# Adorkable_Base.net
KiCad netlist of a schematic drawn in EasyEDA Pro
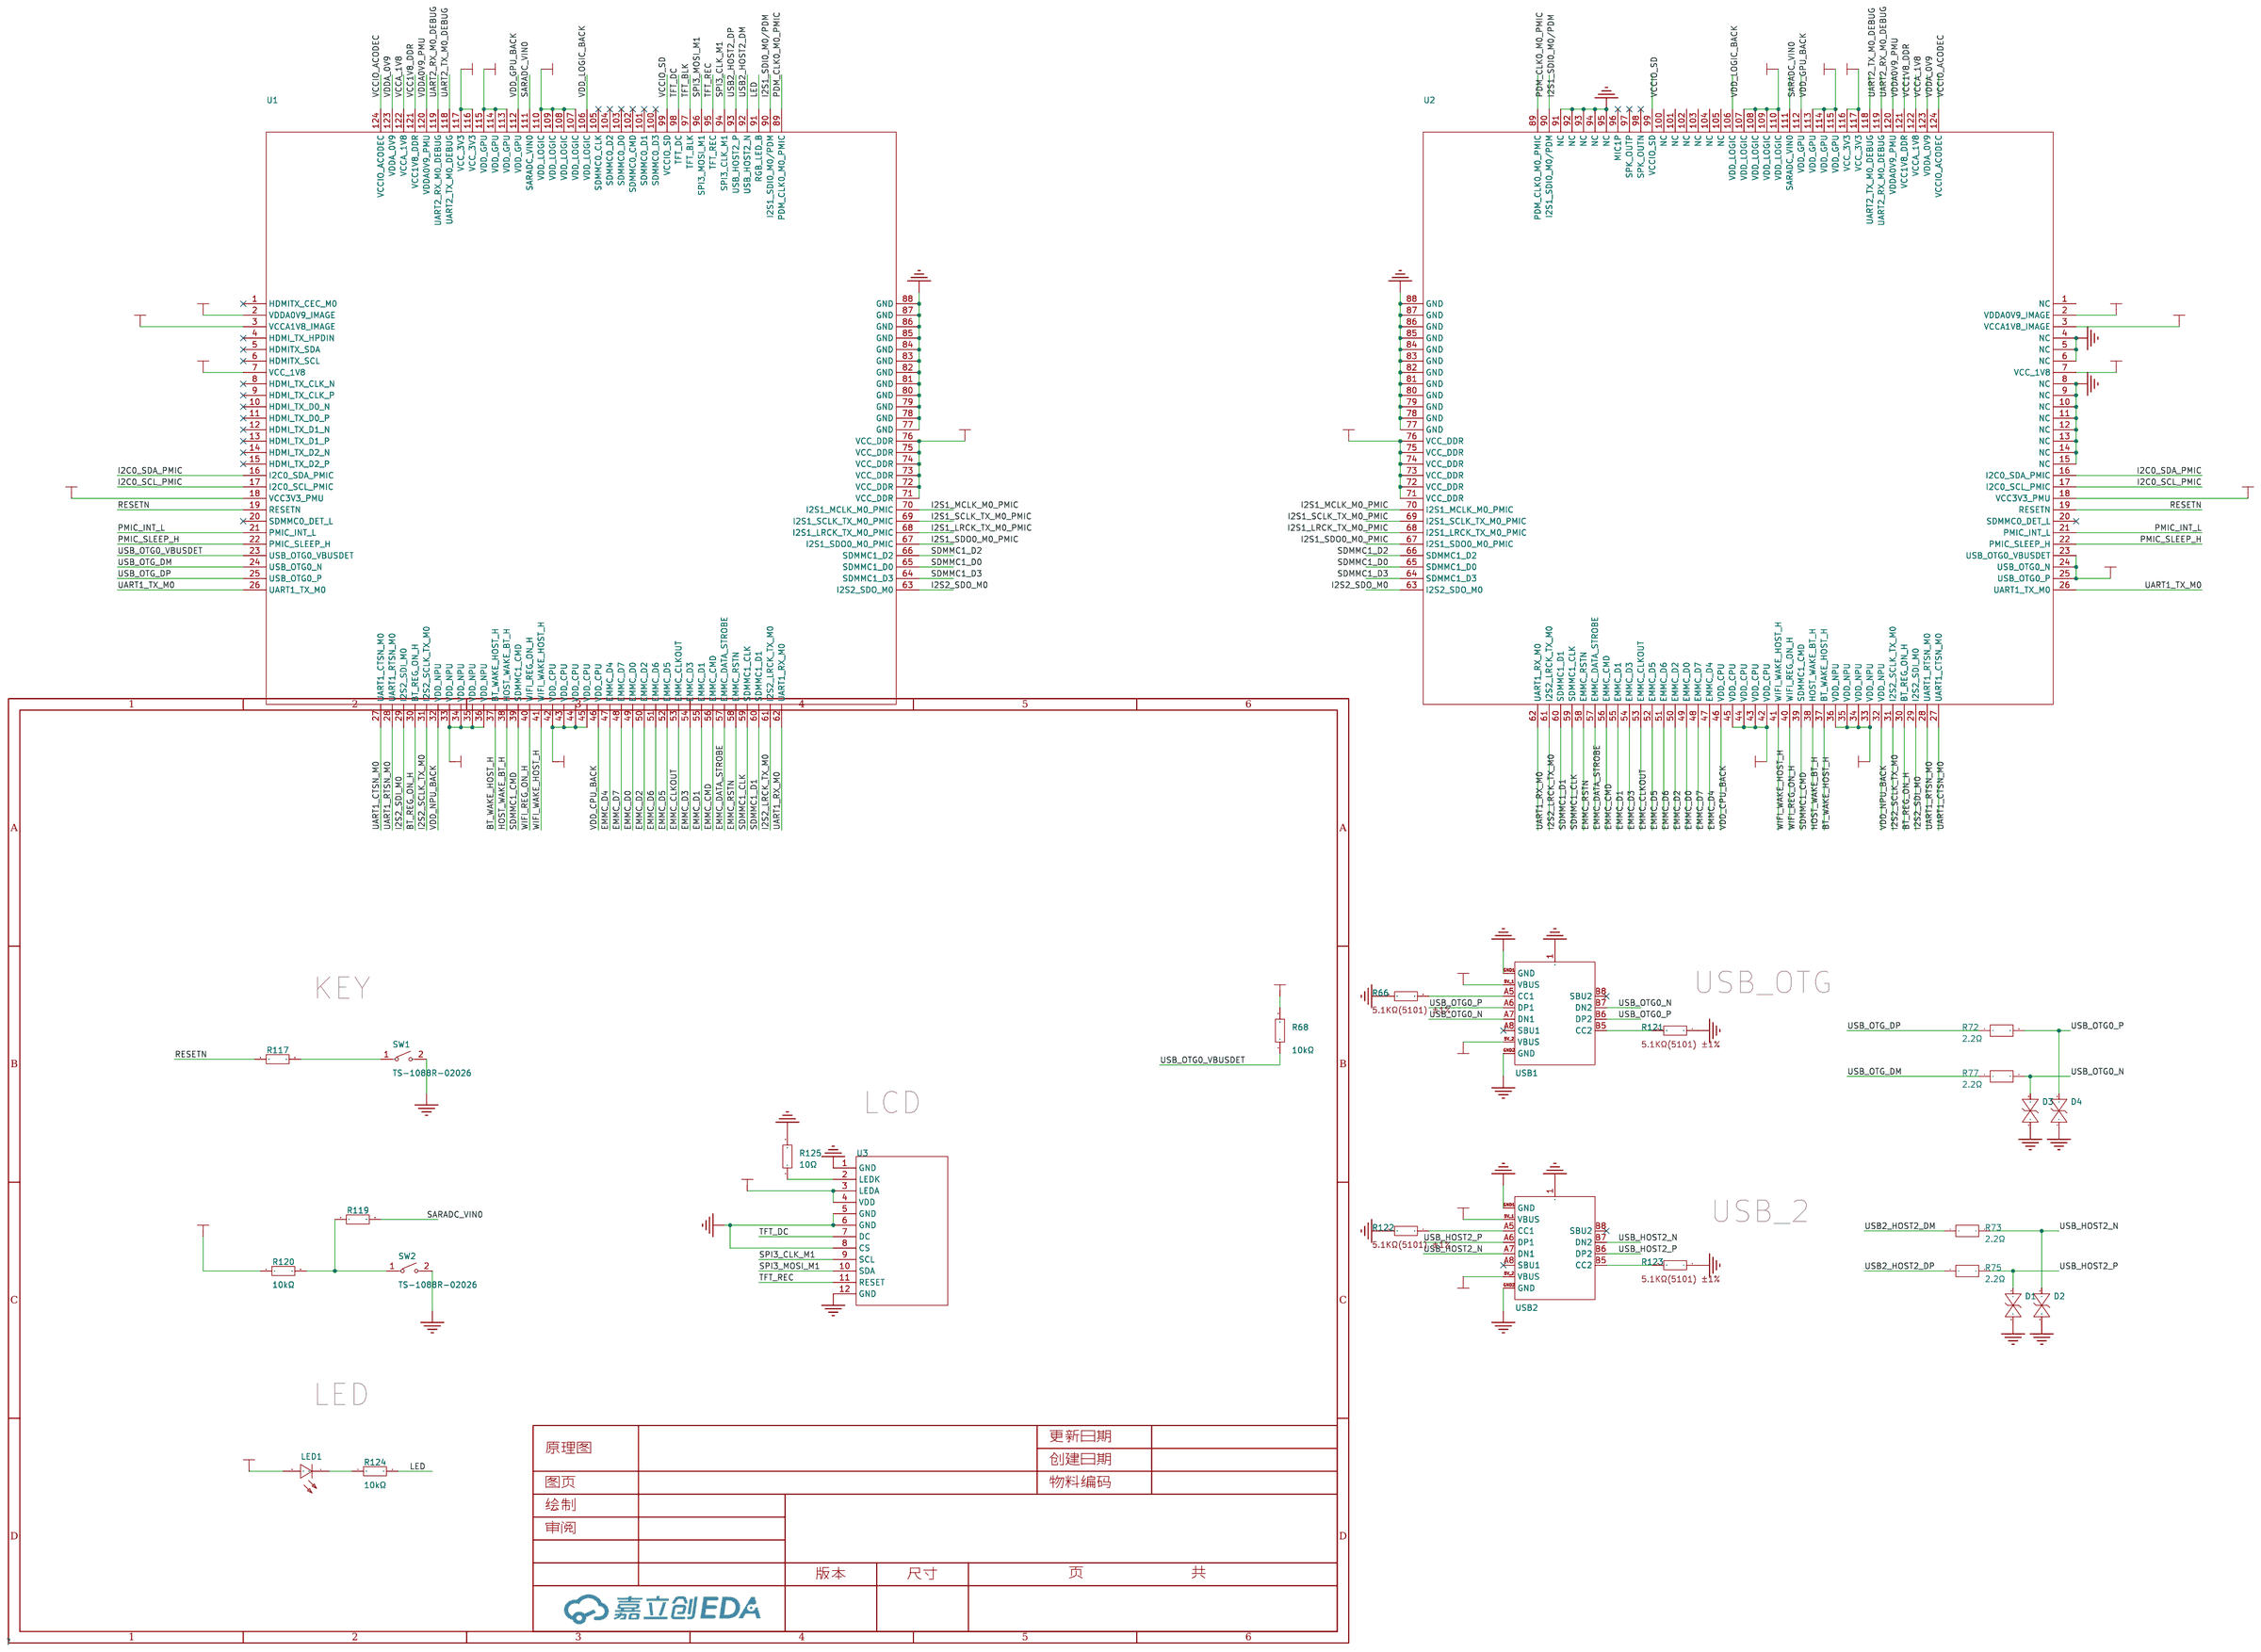
[diagram p0: schematic sheet]

(export (version "E")
  (design (tool "Eeschema 10.0.6"))
  (components
    (comp (ref "D1")
      (value "KLXES15AAA1")
      (footprint "easyedapro:D0402-BI")
      (description "极性:双向;反向截止电压(Vrwm):5V;钳位电压(Vc)@Ipp:40V;")
      (fields (field (name "Manufacturer") "KUU"))
      (libsource (lib "easyedapro") (part "KLXES15AAA1"))
    )
    (comp (ref "D2")
      (value "KLXES15AAA1")
      (footprint "easyedapro:D0402-BI")
      (description "极性:双向;反向截止电压(Vrwm):5V;钳位电压(Vc)@Ipp:40V;")
      (fields (field (name "Manufacturer") "KUU"))
      (libsource (lib "easyedapro") (part "KLXES15AAA1"))
    )
    (comp (ref "D3")
      (value "KLXES15AAA1")
      (footprint "easyedapro:D0402-BI")
      (description "极性:双向;反向截止电压(Vrwm):5V;钳位电压(Vc)@Ipp:40V;")
      (fields (field (name "Manufacturer") "KUU"))
      (libsource (lib "easyedapro") (part "KLXES15AAA1"))
    )
    (comp (ref "D4")
      (value "KLXES15AAA1")
      (footprint "easyedapro:D0402-BI")
      (description "极性:双向;反向截止电压(Vrwm):5V;钳位电压(Vc)@Ipp:40V;")
      (fields (field (name "Manufacturer") "KUU"))
      (libsource (lib "easyedapro") (part "KLXES15AAA1"))
    )
    (comp (ref "LED1")
      (value "19-217/GHC-YR1S2/3T")
      (footprint "easyedapro:LED0603-RD")
      (description "发光颜色:翠绿;二极管配置:-;主波长:520nm~535nm;色温:-;功率:110mW;安装方式:-;")
      (fields (field (name "Manufacturer") "EVERLIGHT(亿光)"))
      (libsource (lib "easyedapro") (part "19-217/GHC-YR1S2/3T"))
    )
    (comp (ref "R66")
      (value "0402WGF5101TCE")
      (footprint "easyedapro:R0402")
      (fields (field (name "Manufacturer") "UNI-ROYAL(厚声)") (field (name "LCSC Part Name") "5.1KΩ(5101) ±1%"))
      (libsource (lib "easyedapro") (part "0402WGF5101TCE"))
    )
    (comp (ref "R68")
      (value "10kΩ")
      (footprint "easyedapro:R0402")
      (description "电阻类型:厚膜电阻;阻值:10kΩ;精度:±1%;功率:63mW;温度系数:±100ppm/K;最大工作电压:50V;工作温度范围:-55°C~+155°C;")
      (fields
        (field (name "Manufacturer Part") "CRCW040210K0FKED")
        (field (name "Manufacturer") "VISHAY(威世)")
      )
      (libsource (lib "easyedapro") (part "CRCW040210K0FKED"))
    )
    (comp (ref "R72")
      (value "2.2Ω")
      (footprint "easyedapro:R0402")
      (description "电阻类型:厚膜电阻;阻值:2.2Ω;精度:±5%;功率:100mW;温度系数:-100ppm/°C~+600ppm/°C;最大工作电压:-;工作温度范围:-55°C~+155°C;")
      (fields (field (name "Manufacturer Part") "ERJ2GEJ2R2X") (field (name "Manufacturer") "PANASONIC(松下)"))
      (libsource (lib "easyedapro") (part "ERJ2GEJ2R2X"))
    )
    (comp (ref "R73")
      (value "2.2Ω")
      (footprint "easyedapro:R0402")
      (description "电阻类型:厚膜电阻;阻值:2.2Ω;精度:±5%;功率:100mW;温度系数:-100ppm/°C~+600ppm/°C;最大工作电压:-;工作温度范围:-55°C~+155°C;")
      (fields (field (name "Manufacturer Part") "ERJ2GEJ2R2X") (field (name "Manufacturer") "PANASONIC(松下)"))
      (libsource (lib "easyedapro") (part "ERJ2GEJ2R2X"))
    )
    (comp (ref "R75")
      (value "2.2Ω")
      (footprint "easyedapro:R0402")
      (description "电阻类型:厚膜电阻;阻值:2.2Ω;精度:±5%;功率:100mW;温度系数:-100ppm/°C~+600ppm/°C;最大工作电压:-;工作温度范围:-55°C~+155°C;")
      (fields (field (name "Manufacturer Part") "ERJ2GEJ2R2X") (field (name "Manufacturer") "PANASONIC(松下)"))
      (libsource (lib "easyedapro") (part "ERJ2GEJ2R2X"))
    )
    (comp (ref "R77")
      (value "2.2Ω")
      (footprint "easyedapro:R0402")
      (description "电阻类型:厚膜电阻;阻值:2.2Ω;精度:±5%;功率:100mW;温度系数:-100ppm/°C~+600ppm/°C;最大工作电压:-;工作温度范围:-55°C~+155°C;")
      (fields (field (name "Manufacturer Part") "ERJ2GEJ2R2X") (field (name "Manufacturer") "PANASONIC(松下)"))
      (libsource (lib "easyedapro") (part "ERJ2GEJ2R2X"))
    )
    (comp (ref "R117")
      (value "0402WGF1000TCE")
      (footprint "easyedapro:R0402")
      (fields (field (name "Manufacturer") "UNI-ROYAL(厚声)"))
      (libsource (lib "easyedapro") (part "0402WGF1000TCE"))
    )
    (comp (ref "R119")
      (value "0402WGF1000TCE")
      (footprint "easyedapro:R0402")
      (fields (field (name "Manufacturer") "UNI-ROYAL(厚声)"))
      (libsource (lib "easyedapro") (part "0402WGF1000TCE"))
    )
    (comp (ref "R120")
      (value "10kΩ")
      (footprint "easyedapro:R0402")
      (description "电阻类型:厚膜电阻;阻值:10kΩ;精度:±1%;功率:62.5mW;")
      (fields
        (field (name "Manufacturer Part") "0402WGF1002TCE")
        (field (name "Manufacturer") "UNI-ROYAL(厚声)")
      )
      (libsource (lib "easyedapro") (part "0402WGF1002TCE"))
    )
    (comp (ref "R121")
      (value "0402WGF5101TCE")
      (footprint "easyedapro:R0402")
      (fields (field (name "Manufacturer") "UNI-ROYAL(厚声)") (field (name "LCSC Part Name") "5.1KΩ(5101) ±1%"))
      (libsource (lib "easyedapro") (part "0402WGF5101TCE"))
    )
    (comp (ref "R122")
      (value "0402WGF5101TCE")
      (footprint "easyedapro:R0402")
      (fields (field (name "Manufacturer") "UNI-ROYAL(厚声)") (field (name "LCSC Part Name") "5.1KΩ(5101) ±1%"))
      (libsource (lib "easyedapro") (part "0402WGF5101TCE"))
    )
    (comp (ref "R123")
      (value "0402WGF5101TCE")
      (footprint "easyedapro:R0402")
      (fields (field (name "Manufacturer") "UNI-ROYAL(厚声)") (field (name "LCSC Part Name") "5.1KΩ(5101) ±1%"))
      (libsource (lib "easyedapro") (part "0402WGF5101TCE"))
    )
    (comp (ref "R124")
      (value "10kΩ")
      (footprint "easyedapro:R0402")
      (description "电阻类型:厚膜电阻;阻值:10kΩ;精度:±1%;功率:62.5mW;")
      (fields
        (field (name "Manufacturer Part") "0402WGF1002TCE")
        (field (name "Manufacturer") "UNI-ROYAL(厚声)")
      )
      (libsource (lib "easyedapro") (part "0402WGF1002TCE"))
    )
    (comp (ref "R125")
      (value "10Ω")
      (footprint "easyedapro:R0402")
      (description "电阻类型:厚膜电阻;阻值:10Ω;精度:±1%;功率:62.5mW;最大工作电压:50V;温度系数:±200ppm/°C;")
      (fields
        (field (name "Manufacturer Part") "0402WGF100JTCE")
        (field (name "Manufacturer") "UNI-ROYAL(厚声)")
      )
      (libsource (lib "easyedapro") (part "0402WGF100JTCE"))
    )
    (comp (ref "SW1")
      (value "TS-1088R-02026")
      (footprint "easyedapro:SW-SMD_L3.9-W3.0-P4.45")
      (description "电路结构:单刀单掷;按钮形状:圆形按钮;安装方式:立贴;开关长度:3.9mm;开关宽度:2.93mm;开关高度:2mm;触点电流:50mA;额定电压(DC):12V;带灯:-;机械寿命:-;")
      (fields (field (name "Manufacturer") "XUNPU(讯普)"))
      (libsource (lib "easyedapro") (part "TS-1088R-02026"))
    )
    (comp (ref "SW2")
      (value "TS-1088R-02026")
      (footprint "easyedapro:SW-SMD_L3.9-W3.0-P4.45")
      (description "电路结构:单刀单掷;按钮形状:圆形按钮;安装方式:立贴;开关长度:3.9mm;开关宽度:2.93mm;开关高度:2mm;触点电流:50mA;额定电压(DC):12V;带灯:-;机械寿命:-;")
      (fields (field (name "Manufacturer") "XUNPU(讯普)"))
      (libsource (lib "easyedapro") (part "TS-1088R-02026"))
    )
    (comp (ref "U1") (value "~") (footprint "easyedapro:Core") (libsource (lib "easyedapro") (part "Core")))
    (comp (ref "U2") (value "~") (footprint "easyedapro:EXP") (libsource (lib "easyedapro") (part "EXP")))
    (comp (ref "U3") (value "~") (footprint "easyedapro:LCD") (libsource (lib "easyedapro") (part "LCD")))
    (comp (ref "USB1")
      (value "~")
      (footprint "easyedapro:TYPE-C-SMD_TYPE-CF3.1")
      (libsource (lib "easyedapro") (part "TYPE-C-16PIN"))
    )
    (comp (ref "USB2")
      (value "~")
      (footprint "easyedapro:TYPE-C-SMD_TYPE-CF3.1")
      (libsource (lib "easyedapro") (part "TYPE-C-16PIN"))
    )
  )
  (nets
    (net (code "1") (name "/BT_REG_ON_H") (class "Default")
      (node (ref "U1") (pin "30") (pinfunction "BT_REG_ON_H_30") (pintype "input"))
      (node (ref "U2") (pin "30") (pinfunction "BT_REG_ON_H_30") (pintype "input"))
    )
    (net (code "2") (name "/BT_WAKE_HOST_H") (class "Default")
      (node (ref "U1") (pin "37") (pinfunction "BT_WAKE_HOST_H_37") (pintype "input"))
      (node (ref "U2") (pin "37") (pinfunction "BT_WAKE_HOST_H_37") (pintype "input"))
    )
    (net (code "3") (name "/EMMC_CLKOUT") (class "Default")
      (node (ref "U1") (pin "53") (pinfunction "EMMC_CLKOUT_53") (pintype "input"))
      (node (ref "U2") (pin "53") (pinfunction "EMMC_CLKOUT_53") (pintype "input"))
    )
    (net (code "4") (name "/EMMC_CMD") (class "Default")
      (node (ref "U1") (pin "56") (pinfunction "EMMC_CMD_56") (pintype "input"))
      (node (ref "U2") (pin "56") (pinfunction "EMMC_CMD_56") (pintype "input"))
    )
    (net (code "5") (name "/EMMC_D0") (class "Default")
      (node (ref "U1") (pin "49") (pinfunction "EMMC_D0_49") (pintype "input"))
      (node (ref "U2") (pin "49") (pinfunction "EMMC_D0_49") (pintype "input"))
    )
    (net (code "6") (name "/EMMC_D1") (class "Default")
      (node (ref "U1") (pin "55") (pinfunction "EMMC_D1_55") (pintype "input"))
      (node (ref "U2") (pin "55") (pinfunction "EMMC_D1_55") (pintype "input"))
    )
    (net (code "7") (name "/EMMC_D2") (class "Default")
      (node (ref "U1") (pin "50") (pinfunction "EMMC_D2_50") (pintype "input"))
      (node (ref "U2") (pin "50") (pinfunction "EMMC_D2_50") (pintype "input"))
    )
    (net (code "8") (name "/EMMC_D3") (class "Default")
      (node (ref "U1") (pin "54") (pinfunction "EMMC_D3_54") (pintype "input"))
      (node (ref "U2") (pin "54") (pinfunction "EMMC_D3_54") (pintype "input"))
    )
    (net (code "9") (name "/EMMC_D4") (class "Default")
      (node (ref "U1") (pin "47") (pinfunction "EMMC_D4_47") (pintype "input"))
      (node (ref "U2") (pin "47") (pinfunction "EMMC_D4_47") (pintype "input"))
    )
    (net (code "10") (name "/EMMC_D5") (class "Default")
      (node (ref "U1") (pin "52") (pinfunction "EMMC_D5_52") (pintype "input"))
      (node (ref "U2") (pin "52") (pinfunction "EMMC_D5_52") (pintype "input"))
    )
    (net (code "11") (name "/EMMC_D6") (class "Default")
      (node (ref "U1") (pin "51") (pinfunction "EMMC_D6_51") (pintype "input"))
      (node (ref "U2") (pin "51") (pinfunction "EMMC_D6_51") (pintype "input"))
    )
    (net (code "12") (name "/EMMC_D7") (class "Default")
      (node (ref "U1") (pin "48") (pinfunction "EMMC_D7_48") (pintype "input"))
      (node (ref "U2") (pin "48") (pinfunction "EMMC_D7_48") (pintype "input"))
    )
    (net (code "13") (name "/EMMC_DATA_STROBE") (class "Default")
      (node (ref "U1") (pin "57") (pinfunction "EMMC_DATA_STROBE_57") (pintype "input"))
      (node (ref "U2") (pin "57") (pinfunction "EMMC_DATA_STROBE_57") (pintype "input"))
    )
    (net (code "14") (name "/EMMC_RSTN") (class "Default")
      (node (ref "U1") (pin "58") (pinfunction "EMMC_RSTN_58") (pintype "input"))
      (node (ref "U2") (pin "58") (pinfunction "EMMC_RSTN_58") (pintype "input"))
    )
    (net (code "15") (name "/HOST_WAKE_BT_H") (class "Default")
      (node (ref "U1") (pin "38") (pinfunction "HOST_WAKE_BT_H_38") (pintype "input"))
      (node (ref "U2") (pin "38") (pinfunction "HOST_WAKE_BT_H_38") (pintype "input"))
    )
    (net (code "16") (name "/I2C0_SCL_PMIC") (class "Default")
      (node (ref "U1") (pin "17") (pinfunction "I2C0_SCL_PMIC_17") (pintype "input"))
      (node (ref "U2") (pin "17") (pinfunction "I2C0_SCL_PMIC_17") (pintype "input"))
    )
    (net (code "17") (name "/I2C0_SDA_PMIC") (class "Default")
      (node (ref "U1") (pin "16") (pinfunction "I2C0_SDA_PMIC_16") (pintype "input"))
      (node (ref "U2") (pin "16") (pinfunction "I2C0_SDA_PMIC_16") (pintype "input"))
    )
    (net (code "18") (name "/I2S1_LRCK_TX_M0_PMIC") (class "Default")
      (node (ref "U1") (pin "68") (pinfunction "I2S1_LRCK_TX_M0_PMIC_68") (pintype "input"))
      (node (ref "U2") (pin "68") (pinfunction "I2S1_LRCK_TX_M0_PMIC_68") (pintype "input"))
    )
    (net (code "19") (name "/I2S1_MCLK_M0_PMIC") (class "Default")
      (node (ref "U1") (pin "70") (pinfunction "I2S1_MCLK_M0_PMIC_70") (pintype "input"))
      (node (ref "U2") (pin "70") (pinfunction "I2S1_MCLK_M0_PMIC_70") (pintype "input"))
    )
    (net (code "20") (name "/I2S1_SCLK_TX_M0_PMIC") (class "Default")
      (node (ref "U1") (pin "69") (pinfunction "I2S1_SCLK_TX_M0_PMIC_69") (pintype "input"))
      (node (ref "U2") (pin "69") (pinfunction "I2S1_SCLK_TX_M0_PMIC_69") (pintype "input"))
    )
    (net (code "21") (name "/I2S1_SDI0_M0{slash}PDM") (class "Default")
      (node (ref "U1") (pin "90") (pinfunction "I2S1_SDI0_M0/PDM_90") (pintype "input"))
      (node (ref "U2") (pin "90") (pinfunction "I2S1_SDI0_M0/PDM_90") (pintype "input"))
    )
    (net (code "22") (name "/I2S1_SDO0_M0_PMIC") (class "Default")
      (node (ref "U1") (pin "67") (pinfunction "I2S1_SDO0_M0_PMIC_67") (pintype "input"))
      (node (ref "U2") (pin "67") (pinfunction "I2S1_SDO0_M0_PMIC_67") (pintype "input"))
    )
    (net (code "23") (name "/I2S2_LRCK_TX_M0") (class "Default")
      (node (ref "U1") (pin "61") (pinfunction "I2S2_LRCK_TX_M0_61") (pintype "input"))
      (node (ref "U2") (pin "61") (pinfunction "I2S2_LRCK_TX_M0_61") (pintype "input"))
    )
    (net (code "24") (name "/I2S2_SCLK_TX_M0") (class "Default")
      (node (ref "U1") (pin "31") (pinfunction "I2S2_SCLK_TX_M0_31") (pintype "input"))
      (node (ref "U2") (pin "31") (pinfunction "I2S2_SCLK_TX_M0_31") (pintype "input"))
    )
    (net (code "25") (name "/I2S2_SDI_M0") (class "Default")
      (node (ref "U1") (pin "29") (pinfunction "I2S2_SDI_M0_29") (pintype "input"))
      (node (ref "U2") (pin "29") (pinfunction "I2S2_SDI_M0_29") (pintype "input"))
    )
    (net (code "26") (name "/I2S2_SDO_M0") (class "Default")
      (node (ref "U1") (pin "63") (pinfunction "I2S2_SDO_M0_63") (pintype "input"))
      (node (ref "U2") (pin "63") (pinfunction "I2S2_SDO_M0_63") (pintype "input"))
    )
    (net (code "27") (name "/LED") (class "Default")
      (node (ref "R124") (pin "2") (pinfunction "2_2") (pintype "input"))
      (node (ref "U1") (pin "91") (pinfunction "RGB_LED_B_91") (pintype "input"))
    )
    (net (code "28") (name "/PDM_CLK0_M0_PMIC") (class "Default")
      (node (ref "U1") (pin "89") (pinfunction "PDM_CLK0_M0_PMIC_89") (pintype "input"))
      (node (ref "U2") (pin "89") (pinfunction "PDM_CLK0_M0_PMIC_89") (pintype "input"))
    )
    (net (code "29") (name "/PMIC_INT_L") (class "Default")
      (node (ref "U1") (pin "21") (pinfunction "PMIC_INT_L_21") (pintype "input"))
      (node (ref "U2") (pin "21") (pinfunction "PMIC_INT_L_21") (pintype "input"))
    )
    (net (code "30") (name "/PMIC_SLEEP_H") (class "Default")
      (node (ref "U1") (pin "22") (pinfunction "PMIC_SLEEP_H_22") (pintype "input"))
      (node (ref "U2") (pin "22") (pinfunction "PMIC_SLEEP_H_22") (pintype "input"))
    )
    (net (code "31") (name "/RESETN") (class "Default")
      (node (ref "R117") (pin "1") (pinfunction "1_1") (pintype "input"))
      (node (ref "U1") (pin "19") (pinfunction "RESETN_19") (pintype "input"))
      (node (ref "U2") (pin "19") (pinfunction "RESETN_19") (pintype "input"))
    )
    (net (code "32") (name "/SARADC_VIN0") (class "Default")
      (node (ref "R119") (pin "2") (pinfunction "2_2") (pintype "input"))
      (node (ref "U1") (pin "111") (pinfunction "SARADC_VIN0_111") (pintype "input"))
      (node (ref "U2") (pin "111") (pinfunction "SARADC_VIN0_111") (pintype "input"))
    )
    (net (code "33") (name "/SDMMC1_CLK") (class "Default")
      (node (ref "U1") (pin "59") (pinfunction "SDMMC1_CLK_59") (pintype "input"))
      (node (ref "U2") (pin "59") (pinfunction "SDMMC1_CLK_59") (pintype "input"))
    )
    (net (code "34") (name "/SDMMC1_CMD") (class "Default")
      (node (ref "U1") (pin "39") (pinfunction "SDMMC1_CMD_39") (pintype "input"))
      (node (ref "U2") (pin "39") (pinfunction "SDMMC1_CMD_39") (pintype "input"))
    )
    (net (code "35") (name "/SDMMC1_D0") (class "Default")
      (node (ref "U1") (pin "65") (pinfunction "SDMMC1_D0_65") (pintype "input"))
      (node (ref "U2") (pin "65") (pinfunction "SDMMC1_D0_65") (pintype "input"))
    )
    (net (code "36") (name "/SDMMC1_D1") (class "Default")
      (node (ref "U1") (pin "60") (pinfunction "SDMMC1_D1_60") (pintype "input"))
      (node (ref "U2") (pin "60") (pinfunction "SDMMC1_D1_60") (pintype "input"))
    )
    (net (code "37") (name "/SDMMC1_D2") (class "Default")
      (node (ref "U1") (pin "66") (pinfunction "SDMMC1_D2_66") (pintype "input"))
      (node (ref "U2") (pin "66") (pinfunction "SDMMC1_D2_66") (pintype "input"))
    )
    (net (code "38") (name "/SDMMC1_D3") (class "Default")
      (node (ref "U1") (pin "64") (pinfunction "SDMMC1_D3_64") (pintype "input"))
      (node (ref "U2") (pin "64") (pinfunction "SDMMC1_D3_64") (pintype "input"))
    )
    (net (code "39") (name "/SPI3_CLK_M1") (class "Default")
      (node (ref "U1") (pin "94") (pinfunction "SPI3_CLK_M1_94") (pintype "input"))
      (node (ref "U3") (pin "9") (pinfunction "SCL_9") (pintype "input"))
    )
    (net (code "40") (name "/SPI3_MOSI_M1") (class "Default")
      (node (ref "U1") (pin "96") (pinfunction "SPI3_MOSI_M1_96") (pintype "input"))
      (node (ref "U3") (pin "10") (pinfunction "SDA_10") (pintype "input"))
    )
    (net (code "41") (name "/TFT_BLK") (class "Default")
      (node (ref "U1") (pin "97") (pinfunction "TFT_BLK_97") (pintype "input"))
    )
    (net (code "42") (name "/TFT_DC") (class "Default")
      (node (ref "U1") (pin "98") (pinfunction "TFT_DC_98") (pintype "input"))
      (node (ref "U3") (pin "7") (pinfunction "DC_7") (pintype "input"))
    )
    (net (code "43") (name "/TFT_REC") (class "Default")
      (node (ref "U1") (pin "95") (pinfunction "TFT_REC_95") (pintype "input"))
      (node (ref "U3") (pin "11") (pinfunction "RESET_11") (pintype "input"))
    )
    (net (code "44") (name "/UART1_CTSN_M0") (class "Default")
      (node (ref "U1") (pin "27") (pinfunction "UART1_CTSN_M0_27") (pintype "input"))
      (node (ref "U2") (pin "27") (pinfunction "UART1_CTSN_M0_27") (pintype "input"))
    )
    (net (code "45") (name "/UART1_RTSN_M0") (class "Default")
      (node (ref "U1") (pin "28") (pinfunction "UART1_RTSN_M0_28") (pintype "input"))
      (node (ref "U2") (pin "28") (pinfunction "UART1_RTSN_M0_28") (pintype "input"))
    )
    (net (code "46") (name "/UART1_RX_M0") (class "Default")
      (node (ref "U1") (pin "62") (pinfunction "UART1_RX_M0_62") (pintype "input"))
      (node (ref "U2") (pin "62") (pinfunction "UART1_RX_M0_62") (pintype "input"))
    )
    (net (code "47") (name "/UART1_TX_M0") (class "Default")
      (node (ref "U1") (pin "26") (pinfunction "UART1_TX_M0_26") (pintype "input"))
      (node (ref "U2") (pin "26") (pinfunction "UART1_TX_M0_26") (pintype "input"))
    )
    (net (code "48") (name "/UART2_RX_M0_DEBUG") (class "Default")
      (node (ref "U1") (pin "119") (pinfunction "UART2_RX_M0_DEBUG_119") (pintype "input"))
      (node (ref "U2") (pin "119") (pinfunction "UART2_RX_M0_DEBUG_119") (pintype "input"))
    )
    (net (code "49") (name "/UART2_TX_M0_DEBUG") (class "Default")
      (node (ref "U1") (pin "118") (pinfunction "UART2_TX_M0_DEBUG_118") (pintype "input"))
      (node (ref "U2") (pin "118") (pinfunction "UART2_TX_M0_DEBUG_118") (pintype "input"))
    )
    (net (code "50") (name "/USB2_HOST2_DM") (class "Default")
      (node (ref "R73") (pin "1") (pinfunction "1_1") (pintype "input"))
      (node (ref "U1") (pin "92") (pinfunction "USB_HOST2_N_92") (pintype "input"))
    )
    (net (code "51") (name "/USB2_HOST2_DP") (class "Default")
      (node (ref "R75") (pin "1") (pinfunction "1_1") (pintype "input"))
      (node (ref "U1") (pin "93") (pinfunction "USB_HOST2_P_93") (pintype "input"))
    )
    (net (code "52") (name "/USB_HOST2_N") (class "Default")
      (node (ref "D2") (pin "2") (pinfunction "A_2") (pintype "input"))
      (node (ref "R73") (pin "2") (pinfunction "2_2") (pintype "input"))
      (node (ref "USB2") (pin "A7") (pinfunction "DN1_A7") (pintype "unspecified"))
      (node (ref "USB2") (pin "B7") (pinfunction "DN2_B7") (pintype "unspecified"))
    )
    (net (code "53") (name "/USB_HOST2_P") (class "Default")
      (node (ref "D1") (pin "2") (pinfunction "A_2") (pintype "input"))
      (node (ref "R75") (pin "2") (pinfunction "2_2") (pintype "input"))
      (node (ref "USB2") (pin "A6") (pinfunction "DP1_A6") (pintype "unspecified"))
      (node (ref "USB2") (pin "B6") (pinfunction "DP2_B6") (pintype "unspecified"))
    )
    (net (code "54") (name "/USB_OTG0_N") (class "Default")
      (node (ref "D3") (pin "2") (pinfunction "A_2") (pintype "input"))
      (node (ref "R77") (pin "2") (pinfunction "2_2") (pintype "input"))
      (node (ref "USB1") (pin "A7") (pinfunction "DN1_A7") (pintype "unspecified"))
      (node (ref "USB1") (pin "B7") (pinfunction "DN2_B7") (pintype "unspecified"))
    )
    (net (code "55") (name "/USB_OTG0_P") (class "Default")
      (node (ref "D4") (pin "2") (pinfunction "A_2") (pintype "input"))
      (node (ref "R72") (pin "2") (pinfunction "2_2") (pintype "input"))
      (node (ref "USB1") (pin "A6") (pinfunction "DP1_A6") (pintype "unspecified"))
      (node (ref "USB1") (pin "B6") (pinfunction "DP2_B6") (pintype "unspecified"))
    )
    (net (code "56") (name "/USB_OTG0_VBUSDET") (class "Default")
      (node (ref "R68") (pin "1") (pinfunction "1_1") (pintype "input"))
      (node (ref "U1") (pin "23") (pinfunction "USB_OTG0_VBUSDET_23") (pintype "input"))
    )
    (net (code "57") (name "/USB_OTG_DM") (class "Default")
      (node (ref "R77") (pin "1") (pinfunction "1_1") (pintype "input"))
      (node (ref "U1") (pin "24") (pinfunction "USB_OTG0_N_24") (pintype "input"))
    )
    (net (code "58") (name "/USB_OTG_DP") (class "Default")
      (node (ref "R72") (pin "1") (pinfunction "1_1") (pintype "input"))
      (node (ref "U1") (pin "25") (pinfunction "USB_OTG0_P_25") (pintype "input"))
    )
    (net (code "59") (name "/VCC1V8_DDR") (class "Default")
      (node (ref "U1") (pin "121") (pinfunction "VCC1V8_DDR_121") (pintype "input"))
      (node (ref "U2") (pin "121") (pinfunction "VCC1V8_DDR_121") (pintype "input"))
    )
    (net (code "60") (name "/VCCIO_ACODEC") (class "Default")
      (node (ref "U1") (pin "124") (pinfunction "VCCIO_ACODEC_124") (pintype "input"))
      (node (ref "U2") (pin "124") (pinfunction "VCCIO_ACODEC_124") (pintype "input"))
    )
    (net (code "61") (name "/VCCIO_SD") (class "Default")
      (node (ref "U1") (pin "99") (pinfunction "VCCIO_SD_99") (pintype "input"))
      (node (ref "U2") (pin "99") (pinfunction "VCCIO_SD_99") (pintype "input"))
    )
    (net (code "62") (name "/VDDA0V9_PMU") (class "Default")
      (node (ref "U1") (pin "120") (pinfunction "VDDA0V9_PMU_120") (pintype "input"))
      (node (ref "U2") (pin "120") (pinfunction "VDDA0V9_PMU_120") (pintype "input"))
    )
    (net (code "63") (name "/VDDA_0V9") (class "Default")
      (node (ref "U1") (pin "123") (pinfunction "VDDA_0V9_123") (pintype "input"))
      (node (ref "U2") (pin "123") (pinfunction "VDDA_0V9_123") (pintype "input"))
    )
    (net (code "64") (name "/VDD_CPU_BACK") (class "Default")
      (node (ref "U1") (pin "46") (pinfunction "VDD_CPU_46") (pintype "input"))
      (node (ref "U2") (pin "46") (pinfunction "VDD_CPU_46") (pintype "input"))
    )
    (net (code "65") (name "/VDD_GPU_BACK") (class "Default")
      (node (ref "U1") (pin "112") (pinfunction "VDD_GPU_112") (pintype "input"))
      (node (ref "U2") (pin "112") (pinfunction "VDD_GPU_112") (pintype "input"))
    )
    (net (code "66") (name "/VDD_LOGIC_BACK") (class "Default")
      (node (ref "U1") (pin "106") (pinfunction "VDD_LOGIC_106") (pintype "input"))
      (node (ref "U2") (pin "106") (pinfunction "VDD_LOGIC_106") (pintype "input"))
    )
    (net (code "67") (name "/VDD_NPU_BACK") (class "Default")
      (node (ref "U1") (pin "32") (pinfunction "VDD_NPU_32") (pintype "input"))
      (node (ref "U2") (pin "32") (pinfunction "VDD_NPU_32") (pintype "input"))
    )
    (net (code "68") (name "/WIFI_REG_ON_H") (class "Default")
      (node (ref "U1") (pin "40") (pinfunction "WIFI_REG_ON_H_40") (pintype "input"))
      (node (ref "U2") (pin "40") (pinfunction "WIFI_REG_ON_H_40") (pintype "input"))
    )
    (net (code "69") (name "/WIFI_WAKE_HOST_H") (class "Default")
      (node (ref "U1") (pin "41") (pinfunction "WIFI_WAKE_HOST_H_41") (pintype "input"))
      (node (ref "U2") (pin "41") (pinfunction "WIFI_WAKE_HOST_H_41") (pintype "input"))
    )
    (net (code "70") (name "GND") (class "Default")
      (node (ref "D1") (pin "1") (pinfunction "K_1") (pintype "input"))
      (node (ref "D2") (pin "1") (pinfunction "K_1") (pintype "input"))
      (node (ref "D3") (pin "1") (pinfunction "K_1") (pintype "input"))
      (node (ref "D4") (pin "1") (pinfunction "K_1") (pintype "input"))
      (node (ref "R121") (pin "1") (pinfunction "1_1") (pintype "input"))
      (node (ref "R122") (pin "2") (pinfunction "2_2") (pintype "input"))
      (node (ref "R123") (pin "1") (pinfunction "1_1") (pintype "input"))
      (node (ref "R125") (pin "2") (pinfunction "2_2") (pintype "input"))
      (node (ref "R66") (pin "2") (pinfunction "2_2") (pintype "input"))
      (node (ref "SW1") (pin "2") (pinfunction "2_2") (pintype "unspecified"))
      (node (ref "SW2") (pin "2") (pinfunction "2_2") (pintype "unspecified"))
      (node (ref "U1") (pin "77") (pinfunction "GND_77") (pintype "input"))
      (node (ref "U1") (pin "78") (pinfunction "GND_78") (pintype "input"))
      (node (ref "U1") (pin "79") (pinfunction "GND_79") (pintype "input"))
      (node (ref "U1") (pin "80") (pinfunction "GND_80") (pintype "input"))
      (node (ref "U1") (pin "81") (pinfunction "GND_81") (pintype "input"))
      (node (ref "U1") (pin "82") (pinfunction "GND_82") (pintype "input"))
      (node (ref "U1") (pin "83") (pinfunction "GND_83") (pintype "input"))
      (node (ref "U1") (pin "84") (pinfunction "GND_84") (pintype "input"))
      (node (ref "U1") (pin "85") (pinfunction "GND_85") (pintype "input"))
      (node (ref "U1") (pin "86") (pinfunction "GND_86") (pintype "input"))
      (node (ref "U1") (pin "87") (pinfunction "GND_87") (pintype "input"))
      (node (ref "U1") (pin "88") (pinfunction "GND_88") (pintype "input"))
      (node (ref "U2") (pin "10") (pinfunction "NC_10") (pintype "input"))
      (node (ref "U2") (pin "11") (pinfunction "NC_11") (pintype "input"))
      (node (ref "U2") (pin "12") (pinfunction "NC_12") (pintype "input"))
      (node (ref "U2") (pin "13") (pinfunction "NC_13") (pintype "input"))
      (node (ref "U2") (pin "14") (pinfunction "NC_14") (pintype "input"))
      (node (ref "U2") (pin "15") (pinfunction "NC_15") (pintype "input"))
      (node (ref "U2") (pin "4") (pinfunction "NC_4") (pintype "input"))
      (node (ref "U2") (pin "5") (pinfunction "NC_5") (pintype "input"))
      (node (ref "U2") (pin "6") (pinfunction "NC_6") (pintype "input"))
      (node (ref "U2") (pin "77") (pinfunction "GND_77") (pintype "input"))
      (node (ref "U2") (pin "78") (pinfunction "GND_78") (pintype "input"))
      (node (ref "U2") (pin "79") (pinfunction "GND_79") (pintype "input"))
      (node (ref "U2") (pin "8") (pinfunction "NC_8") (pintype "input"))
      (node (ref "U2") (pin "80") (pinfunction "GND_80") (pintype "input"))
      (node (ref "U2") (pin "81") (pinfunction "GND_81") (pintype "input"))
      (node (ref "U2") (pin "82") (pinfunction "GND_82") (pintype "input"))
      (node (ref "U2") (pin "83") (pinfunction "GND_83") (pintype "input"))
      (node (ref "U2") (pin "84") (pinfunction "GND_84") (pintype "input"))
      (node (ref "U2") (pin "85") (pinfunction "GND_85") (pintype "input"))
      (node (ref "U2") (pin "86") (pinfunction "GND_86") (pintype "input"))
      (node (ref "U2") (pin "87") (pinfunction "GND_87") (pintype "input"))
      (node (ref "U2") (pin "88") (pinfunction "GND_88") (pintype "input"))
      (node (ref "U2") (pin "9") (pinfunction "NC_9") (pintype "input"))
      (node (ref "U2") (pin "91") (pinfunction "NC_91") (pintype "input"))
      (node (ref "U2") (pin "92") (pinfunction "NC_92") (pintype "input"))
      (node (ref "U2") (pin "93") (pinfunction "NC_93") (pintype "input"))
      (node (ref "U2") (pin "94") (pinfunction "NC_94") (pintype "input"))
      (node (ref "U2") (pin "95") (pinfunction "NC_95") (pintype "input"))
      (node (ref "U3") (pin "1") (pinfunction "GND_1") (pintype "input"))
      (node (ref "U3") (pin "12") (pinfunction "GND_12") (pintype "input"))
      (node (ref "U3") (pin "5") (pinfunction "GND_5") (pintype "input"))
      (node (ref "U3") (pin "6") (pinfunction "GND_6") (pintype "input"))
      (node (ref "U3") (pin "8") (pinfunction "CS_8") (pintype "input"))
      (node (ref "USB1") (pin "1") (pinfunction "EH_1") (pintype "unspecified"))
      (node (ref "USB1") (pin "GND1") (pinfunction "GND_GND1") (pintype "unspecified"))
      (node (ref "USB1") (pin "GND2") (pinfunction "GND_GND2") (pintype "unspecified"))
      (node (ref "USB2") (pin "1") (pinfunction "EH_1") (pintype "unspecified"))
      (node (ref "USB2") (pin "GND1") (pinfunction "GND_GND1") (pintype "unspecified"))
      (node (ref "USB2") (pin "GND2") (pinfunction "GND_GND2") (pintype "unspecified"))
    )
    (net (code "71") (name "Net-(LED1-C)") (class "Default")
      (node (ref "LED1") (pin "1") (pinfunction "C_1") (pintype "input"))
      (node (ref "R124") (pin "1") (pinfunction "1_1") (pintype "input"))
    )
    (net (code "72") (name "Net-(R117-Pad2)") (class "Default")
      (node (ref "R117") (pin "2") (pinfunction "2_2") (pintype "input"))
      (node (ref "SW1") (pin "1") (pinfunction "1_1") (pintype "unspecified"))
    )
    (net (code "73") (name "Net-(R119-Pad1)") (class "Default")
      (node (ref "R119") (pin "1") (pinfunction "1_1") (pintype "input"))
      (node (ref "R120") (pin "2") (pinfunction "2_2") (pintype "input"))
      (node (ref "SW2") (pin "1") (pinfunction "1_1") (pintype "unspecified"))
    )
    (net (code "74") (name "Net-(U3-LEDK)") (class "Default")
      (node (ref "R125") (pin "1") (pinfunction "1_1") (pintype "input"))
      (node (ref "U3") (pin "2") (pinfunction "LEDK_2") (pintype "input"))
    )
    (net (code "75") (name "Net-(USB1-CC1)") (class "Default")
      (node (ref "R66") (pin "1") (pinfunction "1_1") (pintype "input"))
      (node (ref "USB1") (pin "A5") (pinfunction "CC1_A5") (pintype "unspecified"))
    )
    (net (code "76") (name "Net-(USB1-CC2)") (class "Default")
      (node (ref "R121") (pin "2") (pinfunction "2_2") (pintype "input"))
      (node (ref "USB1") (pin "B5") (pinfunction "CC2_B5") (pintype "unspecified"))
    )
    (net (code "77") (name "Net-(USB2-CC1)") (class "Default")
      (node (ref "R122") (pin "1") (pinfunction "1_1") (pintype "input"))
      (node (ref "USB2") (pin "A5") (pinfunction "CC1_A5") (pintype "unspecified"))
    )
    (net (code "78") (name "Net-(USB2-CC2)") (class "Default")
      (node (ref "R123") (pin "2") (pinfunction "2_2") (pintype "input"))
      (node (ref "USB2") (pin "B5") (pinfunction "CC2_B5") (pintype "unspecified"))
    )
    (net (code "79") (name "VCC3V3_PMU") (class "Default")
      (node (ref "U1") (pin "18") (pinfunction "VCC3V3_PMU_18") (pintype "input"))
      (node (ref "U2") (pin "18") (pinfunction "VCC3V3_PMU_18") (pintype "input"))
    )
    (net (code "80") (name "VCCA1V8_IMAGE") (class "Default")
      (node (ref "U1") (pin "3") (pinfunction "VCCA1V8_IMAGE_3") (pintype "input"))
      (node (ref "U2") (pin "3") (pinfunction "VCCA1V8_IMAGE_3") (pintype "input"))
    )
    (net (code "81") (name "VCCA_1V8") (class "Default")
      (node (ref "R120") (pin "1") (pinfunction "1_1") (pintype "input"))
      (node (ref "U1") (pin "122") (pinfunction "VCCA_1V8_122") (pintype "input"))
      (node (ref "U2") (pin "122") (pinfunction "VCCA_1V8_122") (pintype "input"))
    )
    (net (code "82") (name "VCC_1V8") (class "Default")
      (node (ref "U1") (pin "7") (pinfunction "VCC_1V8_7") (pintype "input"))
      (node (ref "U2") (pin "7") (pinfunction "VCC_1V8_7") (pintype "input"))
    )
    (net (code "83") (name "VCC_3V3") (class "Default")
      (node (ref "U1") (pin "116") (pinfunction "VCC_3V3_116") (pintype "input"))
      (node (ref "U1") (pin "117") (pinfunction "VCC_3V3_117") (pintype "input"))
      (node (ref "U2") (pin "116") (pinfunction "VCC_3V3_116") (pintype "input"))
      (node (ref "U2") (pin "117") (pinfunction "VCC_3V3_117") (pintype "input"))
      (node (ref "U3") (pin "3") (pinfunction "LEDA_3") (pintype "input"))
      (node (ref "U3") (pin "4") (pinfunction "VDD_4") (pintype "input"))
    )
    (net (code "84") (name "VCC_5V") (class "Default")
      (node (ref "LED1") (pin "2") (pinfunction "A_2") (pintype "input"))
      (node (ref "R68") (pin "2") (pinfunction "2_2") (pintype "input"))
      (node (ref "U2") (pin "23") (pinfunction "USB_OTG0_VBUSDET_23") (pintype "input"))
      (node (ref "U2") (pin "24") (pinfunction "USB_OTG0_N_24") (pintype "input"))
      (node (ref "U2") (pin "25") (pinfunction "USB_OTG0_P_25") (pintype "input"))
      (node (ref "USB1") (pin "5V_1") (pinfunction "VBUS_5V_1") (pintype "unspecified"))
      (node (ref "USB1") (pin "5V_2") (pinfunction "VBUS_5V_2") (pintype "unspecified"))
      (node (ref "USB2") (pin "5V_1") (pinfunction "VBUS_5V_1") (pintype "unspecified"))
      (node (ref "USB2") (pin "5V_2") (pinfunction "VBUS_5V_2") (pintype "unspecified"))
    )
    (net (code "85") (name "VCC_DDR") (class "Default")
      (node (ref "U1") (pin "71") (pinfunction "VCC_DDR_71") (pintype "input"))
      (node (ref "U1") (pin "72") (pinfunction "VCC_DDR_72") (pintype "input"))
      (node (ref "U1") (pin "73") (pinfunction "VCC_DDR_73") (pintype "input"))
      (node (ref "U1") (pin "74") (pinfunction "VCC_DDR_74") (pintype "input"))
      (node (ref "U1") (pin "75") (pinfunction "VCC_DDR_75") (pintype "input"))
      (node (ref "U1") (pin "76") (pinfunction "VCC_DDR_76") (pintype "input"))
      (node (ref "U2") (pin "71") (pinfunction "VCC_DDR_71") (pintype "input"))
      (node (ref "U2") (pin "72") (pinfunction "VCC_DDR_72") (pintype "input"))
      (node (ref "U2") (pin "73") (pinfunction "VCC_DDR_73") (pintype "input"))
      (node (ref "U2") (pin "74") (pinfunction "VCC_DDR_74") (pintype "input"))
      (node (ref "U2") (pin "75") (pinfunction "VCC_DDR_75") (pintype "input"))
      (node (ref "U2") (pin "76") (pinfunction "VCC_DDR_76") (pintype "input"))
    )
    (net (code "86") (name "VDDA0V9_IMAGE") (class "Default")
      (node (ref "U1") (pin "2") (pinfunction "VDDA0V9_IMAGE_2") (pintype "input"))
      (node (ref "U2") (pin "2") (pinfunction "VDDA0V9_IMAGE_2") (pintype "input"))
    )
    (net (code "87") (name "VDD_CPU") (class "Default")
      (node (ref "U1") (pin "42") (pinfunction "VDD_CPU_42") (pintype "input"))
      (node (ref "U1") (pin "43") (pinfunction "VDD_CPU_43") (pintype "input"))
      (node (ref "U1") (pin "44") (pinfunction "VDD_CPU_44") (pintype "input"))
      (node (ref "U1") (pin "45") (pinfunction "VDD_CPU_45") (pintype "input"))
      (node (ref "U2") (pin "42") (pinfunction "VDD_CPU_42") (pintype "input"))
      (node (ref "U2") (pin "43") (pinfunction "VDD_CPU_43") (pintype "input"))
      (node (ref "U2") (pin "44") (pinfunction "VDD_CPU_44") (pintype "input"))
      (node (ref "U2") (pin "45") (pinfunction "VDD_CPU_45") (pintype "input"))
    )
    (net (code "88") (name "VDD_GPU") (class "Default")
      (node (ref "U1") (pin "113") (pinfunction "VDD_GPU_113") (pintype "input"))
      (node (ref "U1") (pin "114") (pinfunction "VDD_GPU_114") (pintype "input"))
      (node (ref "U1") (pin "115") (pinfunction "VDD_GPU_115") (pintype "input"))
      (node (ref "U2") (pin "113") (pinfunction "VDD_GPU_113") (pintype "input"))
      (node (ref "U2") (pin "114") (pinfunction "VDD_GPU_114") (pintype "input"))
      (node (ref "U2") (pin "115") (pinfunction "VDD_GPU_115") (pintype "input"))
    )
    (net (code "89") (name "VDD_LOGIC") (class "Default")
      (node (ref "U1") (pin "107") (pinfunction "VDD_LOGIC_107") (pintype "input"))
      (node (ref "U1") (pin "108") (pinfunction "VDD_LOGIC_108") (pintype "input"))
      (node (ref "U1") (pin "109") (pinfunction "VDD_LOGIC_109") (pintype "input"))
      (node (ref "U1") (pin "110") (pinfunction "VDD_LOGIC_110") (pintype "input"))
      (node (ref "U2") (pin "107") (pinfunction "VDD_LOGIC_107") (pintype "input"))
      (node (ref "U2") (pin "108") (pinfunction "VDD_LOGIC_108") (pintype "input"))
      (node (ref "U2") (pin "109") (pinfunction "VDD_LOGIC_109") (pintype "input"))
      (node (ref "U2") (pin "110") (pinfunction "VDD_LOGIC_110") (pintype "input"))
    )
    (net (code "90") (name "VDD_NPU") (class "Default")
      (node (ref "U1") (pin "33") (pinfunction "VDD_NPU_33") (pintype "input"))
      (node (ref "U1") (pin "34") (pinfunction "VDD_NPU_34") (pintype "input"))
      (node (ref "U1") (pin "35") (pinfunction "VDD_NPU_35") (pintype "input"))
      (node (ref "U1") (pin "36") (pinfunction "VDD_NPU_36") (pintype "input"))
      (node (ref "U2") (pin "33") (pinfunction "VDD_NPU_33") (pintype "input"))
      (node (ref "U2") (pin "34") (pinfunction "VDD_NPU_34") (pintype "input"))
      (node (ref "U2") (pin "35") (pinfunction "VDD_NPU_35") (pintype "input"))
      (node (ref "U2") (pin "36") (pinfunction "VDD_NPU_36") (pintype "input"))
    )
    (net (code "91") (name "unconnected-(U1-HDMITX_CEC_M0-Pad1)") (class "Default")
      (node (ref "U1") (pin "1") (pinfunction "HDMITX_CEC_M0_1") (pintype "input+no_connect"))
    )
    (net (code "92") (name "unconnected-(U1-HDMITX_SCL-Pad6)") (class "Default")
      (node (ref "U1") (pin "6") (pinfunction "HDMITX_SCL_6") (pintype "input+no_connect"))
    )
    (net (code "93") (name "unconnected-(U1-HDMITX_SDA-Pad5)") (class "Default")
      (node (ref "U1") (pin "5") (pinfunction "HDMITX_SDA_5") (pintype "input+no_connect"))
    )
    (net (code "94") (name "unconnected-(U1-HDMI_TX_CLK_N-Pad8)") (class "Default")
      (node (ref "U1") (pin "8") (pinfunction "HDMI_TX_CLK_N_8") (pintype "input+no_connect"))
    )
    (net (code "95") (name "unconnected-(U1-HDMI_TX_CLK_P-Pad9)") (class "Default")
      (node (ref "U1") (pin "9") (pinfunction "HDMI_TX_CLK_P_9") (pintype "input+no_connect"))
    )
    (net (code "96") (name "unconnected-(U1-HDMI_TX_D0_N-Pad10)") (class "Default")
      (node (ref "U1") (pin "10") (pinfunction "HDMI_TX_D0_N_10") (pintype "input+no_connect"))
    )
    (net (code "97") (name "unconnected-(U1-HDMI_TX_D0_P-Pad11)") (class "Default")
      (node (ref "U1") (pin "11") (pinfunction "HDMI_TX_D0_P_11") (pintype "input+no_connect"))
    )
    (net (code "98") (name "unconnected-(U1-HDMI_TX_D1_N-Pad12)") (class "Default")
      (node (ref "U1") (pin "12") (pinfunction "HDMI_TX_D1_N_12") (pintype "input+no_connect"))
    )
    (net (code "99") (name "unconnected-(U1-HDMI_TX_D1_P-Pad13)") (class "Default")
      (node (ref "U1") (pin "13") (pinfunction "HDMI_TX_D1_P_13") (pintype "input+no_connect"))
    )
    (net (code "100") (name "unconnected-(U1-HDMI_TX_D2_N-Pad14)") (class "Default")
      (node (ref "U1") (pin "14") (pinfunction "HDMI_TX_D2_N_14") (pintype "input+no_connect"))
    )
    (net (code "101") (name "unconnected-(U1-HDMI_TX_D2_P-Pad15)") (class "Default")
      (node (ref "U1") (pin "15") (pinfunction "HDMI_TX_D2_P_15") (pintype "input+no_connect"))
    )
    (net (code "102") (name "unconnected-(U1-HDMI_TX_HPDIN-Pad4)") (class "Default")
      (node (ref "U1") (pin "4") (pinfunction "HDMI_TX_HPDIN_4") (pintype "input+no_connect"))
    )
    (net (code "103") (name "unconnected-(U1-SDMMC0_CLK-Pad105)") (class "Default")
      (node (ref "U1") (pin "105") (pinfunction "SDMMC0_CLK_105") (pintype "input+no_connect"))
    )
    (net (code "104") (name "unconnected-(U1-SDMMC0_CMD-Pad102)") (class "Default")
      (node (ref "U1") (pin "102") (pinfunction "SDMMC0_CMD_102") (pintype "input+no_connect"))
    )
    (net (code "105") (name "unconnected-(U1-SDMMC0_D0-Pad103)") (class "Default")
      (node (ref "U1") (pin "103") (pinfunction "SDMMC0_D0_103") (pintype "input+no_connect"))
    )
    (net (code "106") (name "unconnected-(U1-SDMMC0_D1-Pad101)") (class "Default")
      (node (ref "U1") (pin "101") (pinfunction "SDMMC0_D1_101") (pintype "input+no_connect"))
    )
    (net (code "107") (name "unconnected-(U1-SDMMC0_D2-Pad104)") (class "Default")
      (node (ref "U1") (pin "104") (pinfunction "SDMMC0_D2_104") (pintype "input+no_connect"))
    )
    (net (code "108") (name "unconnected-(U1-SDMMC0_D3-Pad100)") (class "Default")
      (node (ref "U1") (pin "100") (pinfunction "SDMMC0_D3_100") (pintype "input+no_connect"))
    )
    (net (code "109") (name "unconnected-(U1-SDMMC0_DET_L-Pad20)") (class "Default")
      (node (ref "U1") (pin "20") (pinfunction "SDMMC0_DET_L_20") (pintype "input+no_connect"))
    )
    (net (code "110") (name "unconnected-(U2-MIC1P-Pad96)") (class "Default")
      (node (ref "U2") (pin "96") (pinfunction "MIC1P_96") (pintype "input+no_connect"))
    )
    (net (code "111") (name "unconnected-(U2-NC-Pad1)") (class "Default")
      (node (ref "U2") (pin "1") (pinfunction "NC_1") (pintype "input"))
    )
    (net (code "112") (name "unconnected-(U2-NC-Pad100)") (class "Default")
      (node (ref "U2") (pin "100") (pinfunction "NC_100") (pintype "input"))
    )
    (net (code "113") (name "unconnected-(U2-NC-Pad101)") (class "Default")
      (node (ref "U2") (pin "101") (pinfunction "NC_101") (pintype "input"))
    )
    (net (code "114") (name "unconnected-(U2-NC-Pad102)") (class "Default")
      (node (ref "U2") (pin "102") (pinfunction "NC_102") (pintype "input"))
    )
    (net (code "115") (name "unconnected-(U2-NC-Pad103)") (class "Default")
      (node (ref "U2") (pin "103") (pinfunction "NC_103") (pintype "input"))
    )
    (net (code "116") (name "unconnected-(U2-NC-Pad104)") (class "Default")
      (node (ref "U2") (pin "104") (pinfunction "NC_104") (pintype "input"))
    )
    (net (code "117") (name "unconnected-(U2-NC-Pad105)") (class "Default")
      (node (ref "U2") (pin "105") (pinfunction "NC_105") (pintype "input"))
    )
    (net (code "118") (name "unconnected-(U2-SDMMC0_DET_L-Pad20)") (class "Default")
      (node (ref "U2") (pin "20") (pinfunction "SDMMC0_DET_L_20") (pintype "input+no_connect"))
    )
    (net (code "119") (name "unconnected-(U2-SPK_OUTN-Pad98)") (class "Default")
      (node (ref "U2") (pin "98") (pinfunction "SPK_OUTN_98") (pintype "input+no_connect"))
    )
    (net (code "120") (name "unconnected-(U2-SPK_OUTP-Pad97)") (class "Default")
      (node (ref "U2") (pin "97") (pinfunction "SPK_OUTP_97") (pintype "input+no_connect"))
    )
    (net (code "121") (name "unconnected-(USB1-SBU1-PadA8)") (class "Default")
      (node (ref "USB1") (pin "A8") (pinfunction "SBU1_A8") (pintype "unspecified+no_connect"))
    )
    (net (code "122") (name "unconnected-(USB1-SBU2-PadB8)") (class "Default")
      (node (ref "USB1") (pin "B8") (pinfunction "SBU2_B8") (pintype "unspecified+no_connect"))
    )
    (net (code "123") (name "unconnected-(USB2-SBU1-PadA8)") (class "Default")
      (node (ref "USB2") (pin "A8") (pinfunction "SBU1_A8") (pintype "unspecified+no_connect"))
    )
    (net (code "124") (name "unconnected-(USB2-SBU2-PadB8)") (class "Default")
      (node (ref "USB2") (pin "B8") (pinfunction "SBU2_B8") (pintype "unspecified+no_connect"))
    )
  )
)
